# connector.net
KiCad netlist of a schematic drawn in Altium Designer
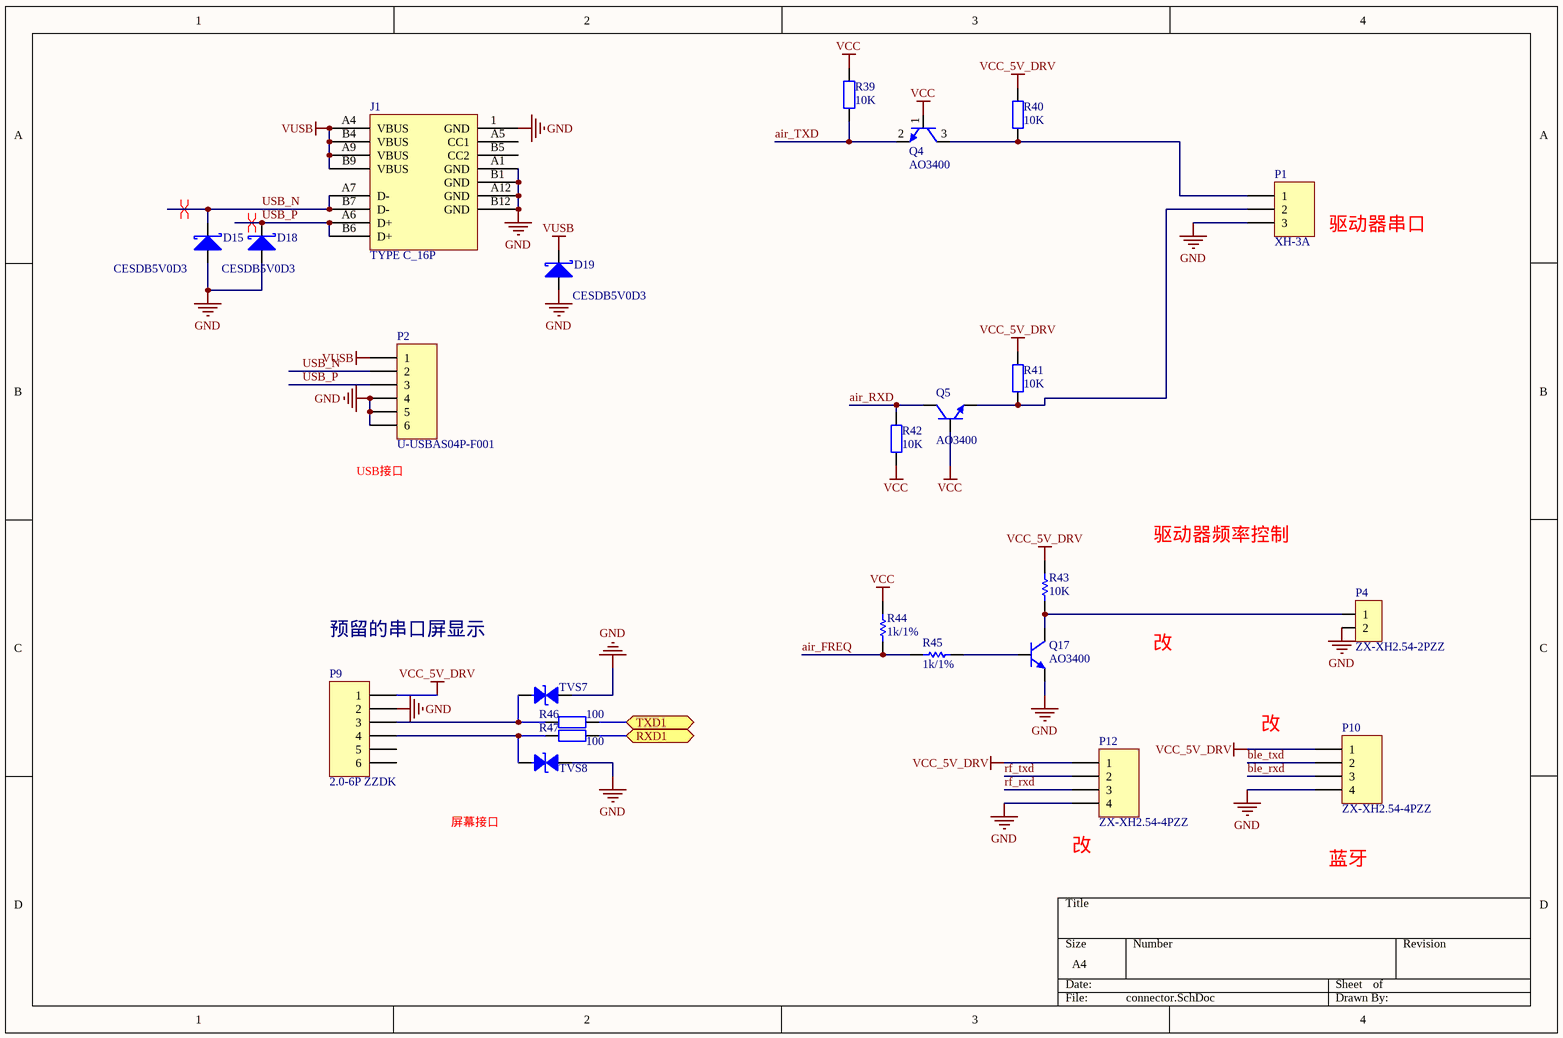
[diagram p0: connector.SchDoc]

(export (version "E")
  (design (tool "Eeschema 10.0.6"))
  (components
    (comp (ref "D15")
      (value "CESDB5V0D3")
      (footprint "SOD323")
      (description "Schottky Diode")
      (libsource (lib "*") (part "DIODE S"))
    )
    (comp (ref "D18")
      (value "CESDB5V0D3")
      (footprint "SOD323")
      (description "Schottky Diode")
      (libsource (lib "*") (part "DIODE S"))
    )
    (comp (ref "D19")
      (value "CESDB5V0D3")
      (footprint "SOD323")
      (description "Schottky Diode")
      (libsource (lib "*") (part "DIODE S"))
    )
    (comp (ref "J1")
      (value "TYPE C_16P")
      (footprint "TYPEC_16P")
      (libsource (lib "Schlib_20110825") (part "TYPE C_16P"))
    )
    (comp (ref "P1")
      (value "XH-3A")
      (footprint "3X2.54MMZ")
      (description "Header, 3-Pin")
      (fields (field (name "PUBLISHER") "Altium Limited"))
      (libsource (lib "Miscellaneous Connectors") (part "Header 3"))
    )
    (comp (ref "P2")
      (value "U-USBAS04P-F001")
      (footprint "USB-A")
      (description "Header, 6-Pin")
      (fields (field (name "PUBLISHER") "Altium Limited"))
      (libsource (lib "") (part "Header 6_1"))
    )
    (comp (ref "P4")
      (value "ZX-XH2.54-2PZZ")
      (footprint "SIP-2A")
      (description "XH2.54 2P 立贴")
      (libsource (lib "XiaoyI") (part "SIP-2"))
    )
    (comp (ref "P9")
      (value "2.0-6P ZZDK")
      (footprint "6X2MMZ")
      (description "Header, 6-Pin")
      (fields (field (name "PUBLISHER") "Altium Limited"))
      (libsource (lib "Miscellaneous Connectors") (part "Header 6"))
    )
    (comp (ref "P10")
      (value "ZX-XH2.54-4PZZ")
      (footprint "4X2.54MMZ")
      (description "Header, 4-Pin")
      (fields (field (name "PUBLISHER") "Altium Limited"))
      (libsource (lib "Miscellaneous Connectors") (part "Header 4"))
    )
    (comp (ref "P12")
      (value "ZX-XH2.54-4PZZ")
      (footprint "4X2.54MMZ")
      (description "Header, 4-Pin")
      (fields (field (name "PUBLISHER") "Altium Limited"))
      (libsource (lib "Miscellaneous Connectors") (part "Header 4"))
    )
    (comp (ref "Q4")
      (value "AO3400")
      (footprint "SOT-23")
      (description "NPN")
      (libsource (lib "XiaoyI") (part "NPN-1"))
    )
    (comp (ref "Q5")
      (value "AO3400")
      (footprint "SOT-23")
      (description "NPN")
      (libsource (lib "") (part "NPN-1_1"))
    )
    (comp (ref "Q17")
      (value "AO3400")
      (footprint "SOT23-3")
      (description "NPN")
      (libsource (lib "") (part "NPN-1_1"))
    )
    (comp (ref "R39")
      (value "10K")
      (footprint "0603r")
      (description "贴片电阻 1%")
      (libsource (lib "XiaoyI") (part "RES2"))
    )
    (comp (ref "R40")
      (value "10K")
      (footprint "0603r")
      (description "贴片电阻 1%")
      (libsource (lib "XiaoyI") (part "RES2"))
    )
    (comp (ref "R41")
      (value "10K")
      (footprint "0603r")
      (description "贴片电阻 1%")
      (libsource (lib "XiaoyI") (part "RES2"))
    )
    (comp (ref "R42")
      (value "10K")
      (footprint "0603r")
      (description "贴片电阻 1%")
      (libsource (lib "XiaoyI") (part "RES2"))
    )
    (comp (ref "R43")
      (value "10K")
      (footprint "0603R")
      (description "Resistor")
      (fields (field (name "PUBLISHER") "Altium Limited"))
      (libsource (lib "Miscellaneous Devices") (part "Res1"))
    )
    (comp (ref "R44")
      (value "1k/1%")
      (footprint "0603R")
      (description "Resistor")
      (fields (field (name "PUBLISHER") "Altium Limited"))
      (libsource (lib "Miscellaneous Devices") (part "Res1"))
    )
    (comp (ref "R45")
      (value "1k/1%")
      (footprint "0603R")
      (description "Resistor")
      (fields (field (name "PUBLISHER") "Altium Limited"))
      (libsource (lib "Miscellaneous Devices") (part "Res1"))
    )
    (comp (ref "R46")
      (value "100")
      (footprint "0603R")
      (description "贴片电阻 5%")
      (libsource (lib "") (part "RES2_1"))
    )
    (comp (ref "R47")
      (value "100")
      (footprint "0603R")
      (description "贴片电阻 5%")
      (libsource (lib "") (part "RES2_1"))
    )
    (comp (ref "TVS7")
      (value "ESD5Z5.0CT1G")
      (footprint "SOD-523")
      (description "TVS")
      (libsource (lib "XiaoyI") (part "TVS-1"))
    )
    (comp (ref "TVS8")
      (value "ESD5Z5.0CT1G")
      (footprint "SOD-523")
      (description "TVS")
      (libsource (lib "XiaoyI") (part "TVS-1"))
    )
  )
  (nets
    (net (code "1") (name "/RXD1") (class "Default")
      (node (ref "R47") (pin "2") (pinfunction "2_2") (pintype "passive"))
    )
    (net (code "2") (name "/TXD1") (class "Default")
      (node (ref "R46") (pin "2") (pinfunction "2_2") (pintype "passive"))
    )
    (net (code "3") (name "/USB_N") (class "Default")
      (node (ref "D15") (pin "2") (pinfunction "K_2") (pintype "passive"))
      (node (ref "J1") (pin "A7") (pinfunction "D-_A7") (pintype "passive"))
      (node (ref "J1") (pin "B7") (pinfunction "D-_B7") (pintype "passive"))
      (node (ref "P2") (pin "2") (pinfunction "2_2") (pintype "passive"))
    )
    (net (code "4") (name "/USB_P") (class "Default")
      (node (ref "D18") (pin "2") (pinfunction "K_2") (pintype "passive"))
      (node (ref "J1") (pin "A6") (pinfunction "D+_A6") (pintype "passive"))
      (node (ref "J1") (pin "B6") (pinfunction "D+_B6") (pintype "passive"))
      (node (ref "P2") (pin "3") (pinfunction "3_3") (pintype "passive"))
    )
    (net (code "5") (name "/air_FREQ") (class "Default")
      (node (ref "R44") (pin "2") (pinfunction "2_2") (pintype "passive"))
      (node (ref "R45") (pin "2") (pinfunction "2_2") (pintype "passive"))
    )
    (net (code "6") (name "/air_RXD") (class "Default")
      (node (ref "Q5") (pin "3") (pinfunction "C_3") (pintype "passive"))
      (node (ref "R42") (pin "2") (pinfunction "2_2") (pintype "passive"))
    )
    (net (code "7") (name "/air_TXD") (class "Default")
      (node (ref "Q4") (pin "2") (pinfunction "E_2") (pintype "passive"))
      (node (ref "R39") (pin "1") (pinfunction "1_1") (pintype "passive"))
    )
    (net (code "8") (name "/ble_rxd") (class "Default")
      (node (ref "P10") (pin "3") (pinfunction "3_3") (pintype "passive"))
    )
    (net (code "9") (name "/ble_txd") (class "Default")
      (node (ref "P10") (pin "2") (pinfunction "2_2") (pintype "passive"))
    )
    (net (code "10") (name "/rf_rxd") (class "Default")
      (node (ref "P12") (pin "3") (pinfunction "3_3") (pintype "passive"))
    )
    (net (code "11") (name "/rf_txd") (class "Default")
      (node (ref "P12") (pin "2") (pinfunction "2_2") (pintype "passive"))
    )
    (net (code "12") (name "GND") (class "Default")
      (node (ref "D15") (pin "1") (pinfunction "A_1") (pintype "passive"))
      (node (ref "D18") (pin "1") (pinfunction "A_1") (pintype "passive"))
      (node (ref "D19") (pin "1") (pinfunction "A_1") (pintype "passive"))
      (node (ref "J1") (pin "1") (pinfunction "GND_1") (pintype "passive"))
      (node (ref "J1") (pin "A1") (pinfunction "GND_A1") (pintype "passive"))
      (node (ref "J1") (pin "A12") (pinfunction "GND_A12") (pintype "passive"))
      (node (ref "J1") (pin "B1") (pinfunction "GND_B1") (pintype "passive"))
      (node (ref "J1") (pin "B12") (pinfunction "GND_B12") (pintype "passive"))
      (node (ref "P1") (pin "3") (pinfunction "3_3") (pintype "passive"))
      (node (ref "P10") (pin "4") (pinfunction "4_4") (pintype "passive"))
      (node (ref "P12") (pin "4") (pinfunction "4_4") (pintype "passive"))
      (node (ref "P2") (pin "4") (pinfunction "4_4") (pintype "passive"))
      (node (ref "P2") (pin "5") (pinfunction "5_5") (pintype "passive"))
      (node (ref "P2") (pin "6") (pinfunction "6_6") (pintype "passive"))
      (node (ref "P4") (pin "2") (pinfunction "2_2") (pintype "passive"))
      (node (ref "P9") (pin "2") (pinfunction "2_2") (pintype "passive"))
      (node (ref "Q17") (pin "2") (pinfunction "E_2") (pintype "passive"))
      (node (ref "TVS7") (pin "1") (pinfunction "A_1") (pintype "passive"))
      (node (ref "TVS8") (pin "1") (pinfunction "A_1") (pintype "passive"))
    )
    (net (code "13") (name "Net-(Q4-C)") (class "Default")
      (node (ref "P1") (pin "1") (pinfunction "1_1") (pintype "passive"))
      (node (ref "Q4") (pin "3") (pinfunction "C_3") (pintype "passive"))
      (node (ref "R40") (pin "1") (pinfunction "1_1") (pintype "passive"))
    )
    (net (code "14") (name "Net-(Q5-E)") (class "Default")
      (node (ref "P1") (pin "2") (pinfunction "2_2") (pintype "passive"))
      (node (ref "Q5") (pin "2") (pinfunction "E_2") (pintype "passive"))
      (node (ref "R41") (pin "1") (pinfunction "1_1") (pintype "passive"))
    )
    (net (code "15") (name "Net-(Q17-B)") (class "Default")
      (node (ref "Q17") (pin "1") (pinfunction "B_1") (pintype "passive"))
      (node (ref "R45") (pin "1") (pinfunction "1_1") (pintype "passive"))
    )
    (net (code "16") (name "Net-(Q17-C)") (class "Default")
      (node (ref "P4") (pin "1") (pinfunction "1_1") (pintype "passive"))
      (node (ref "Q17") (pin "3") (pinfunction "C_3") (pintype "passive"))
      (node (ref "R43") (pin "1") (pinfunction "1_1") (pintype "passive"))
    )
    (net (code "17") (name "Net-(TVS7-B)") (class "Default")
      (node (ref "P9") (pin "3") (pinfunction "3_3") (pintype "passive"))
      (node (ref "R46") (pin "1") (pinfunction "1_1") (pintype "passive"))
      (node (ref "TVS7") (pin "2") (pinfunction "B_2") (pintype "passive"))
    )
    (net (code "18") (name "Net-(TVS8-B)") (class "Default")
      (node (ref "P9") (pin "4") (pinfunction "4_4") (pintype "passive"))
      (node (ref "R47") (pin "1") (pinfunction "1_1") (pintype "passive"))
      (node (ref "TVS8") (pin "2") (pinfunction "B_2") (pintype "passive"))
    )
    (net (code "19") (name "VCC") (class "Default")
      (node (ref "Q4") (pin "1") (pinfunction "B_1") (pintype "passive"))
      (node (ref "Q5") (pin "1") (pinfunction "B_1") (pintype "passive"))
      (node (ref "R39") (pin "2") (pinfunction "2_2") (pintype "passive"))
      (node (ref "R42") (pin "1") (pinfunction "1_1") (pintype "passive"))
      (node (ref "R44") (pin "1") (pinfunction "1_1") (pintype "passive"))
    )
    (net (code "20") (name "VCC_5V_DRV") (class "Default")
      (node (ref "P10") (pin "1") (pinfunction "1_1") (pintype "passive"))
      (node (ref "P12") (pin "1") (pinfunction "1_1") (pintype "passive"))
      (node (ref "P9") (pin "1") (pinfunction "1_1") (pintype "passive"))
      (node (ref "R40") (pin "2") (pinfunction "2_2") (pintype "passive"))
      (node (ref "R41") (pin "2") (pinfunction "2_2") (pintype "passive"))
      (node (ref "R43") (pin "2") (pinfunction "2_2") (pintype "passive"))
    )
    (net (code "21") (name "VUSB") (class "Default")
      (node (ref "D19") (pin "2") (pinfunction "K_2") (pintype "passive"))
      (node (ref "J1") (pin "A4") (pinfunction "VBUS_A4") (pintype "passive"))
      (node (ref "J1") (pin "A9") (pinfunction "VBUS_A9") (pintype "passive"))
      (node (ref "J1") (pin "B4") (pinfunction "VBUS_B4") (pintype "passive"))
      (node (ref "J1") (pin "B9") (pinfunction "VBUS_B9") (pintype "passive"))
      (node (ref "P2") (pin "1") (pinfunction "1_1") (pintype "passive"))
    )
    (net (code "22") (name "unconnected-(J1-CC1-PadA5)") (class "Default")
      (node (ref "J1") (pin "A5") (pinfunction "CC1_A5") (pintype "passive"))
    )
    (net (code "23") (name "unconnected-(J1-CC2-PadB5)") (class "Default")
      (node (ref "J1") (pin "B5") (pinfunction "CC2_B5") (pintype "passive"))
    )
    (net (code "24") (name "unconnected-(P9-Pad5)") (class "Default")
      (node (ref "P9") (pin "5") (pinfunction "5_5") (pintype "passive"))
    )
    (net (code "25") (name "unconnected-(P9-Pad6)") (class "Default")
      (node (ref "P9") (pin "6") (pinfunction "6_6") (pintype "passive"))
    )
  )
)
